# StressMonitor.net
KiCad netlist of a schematic drawn in Altium Designer
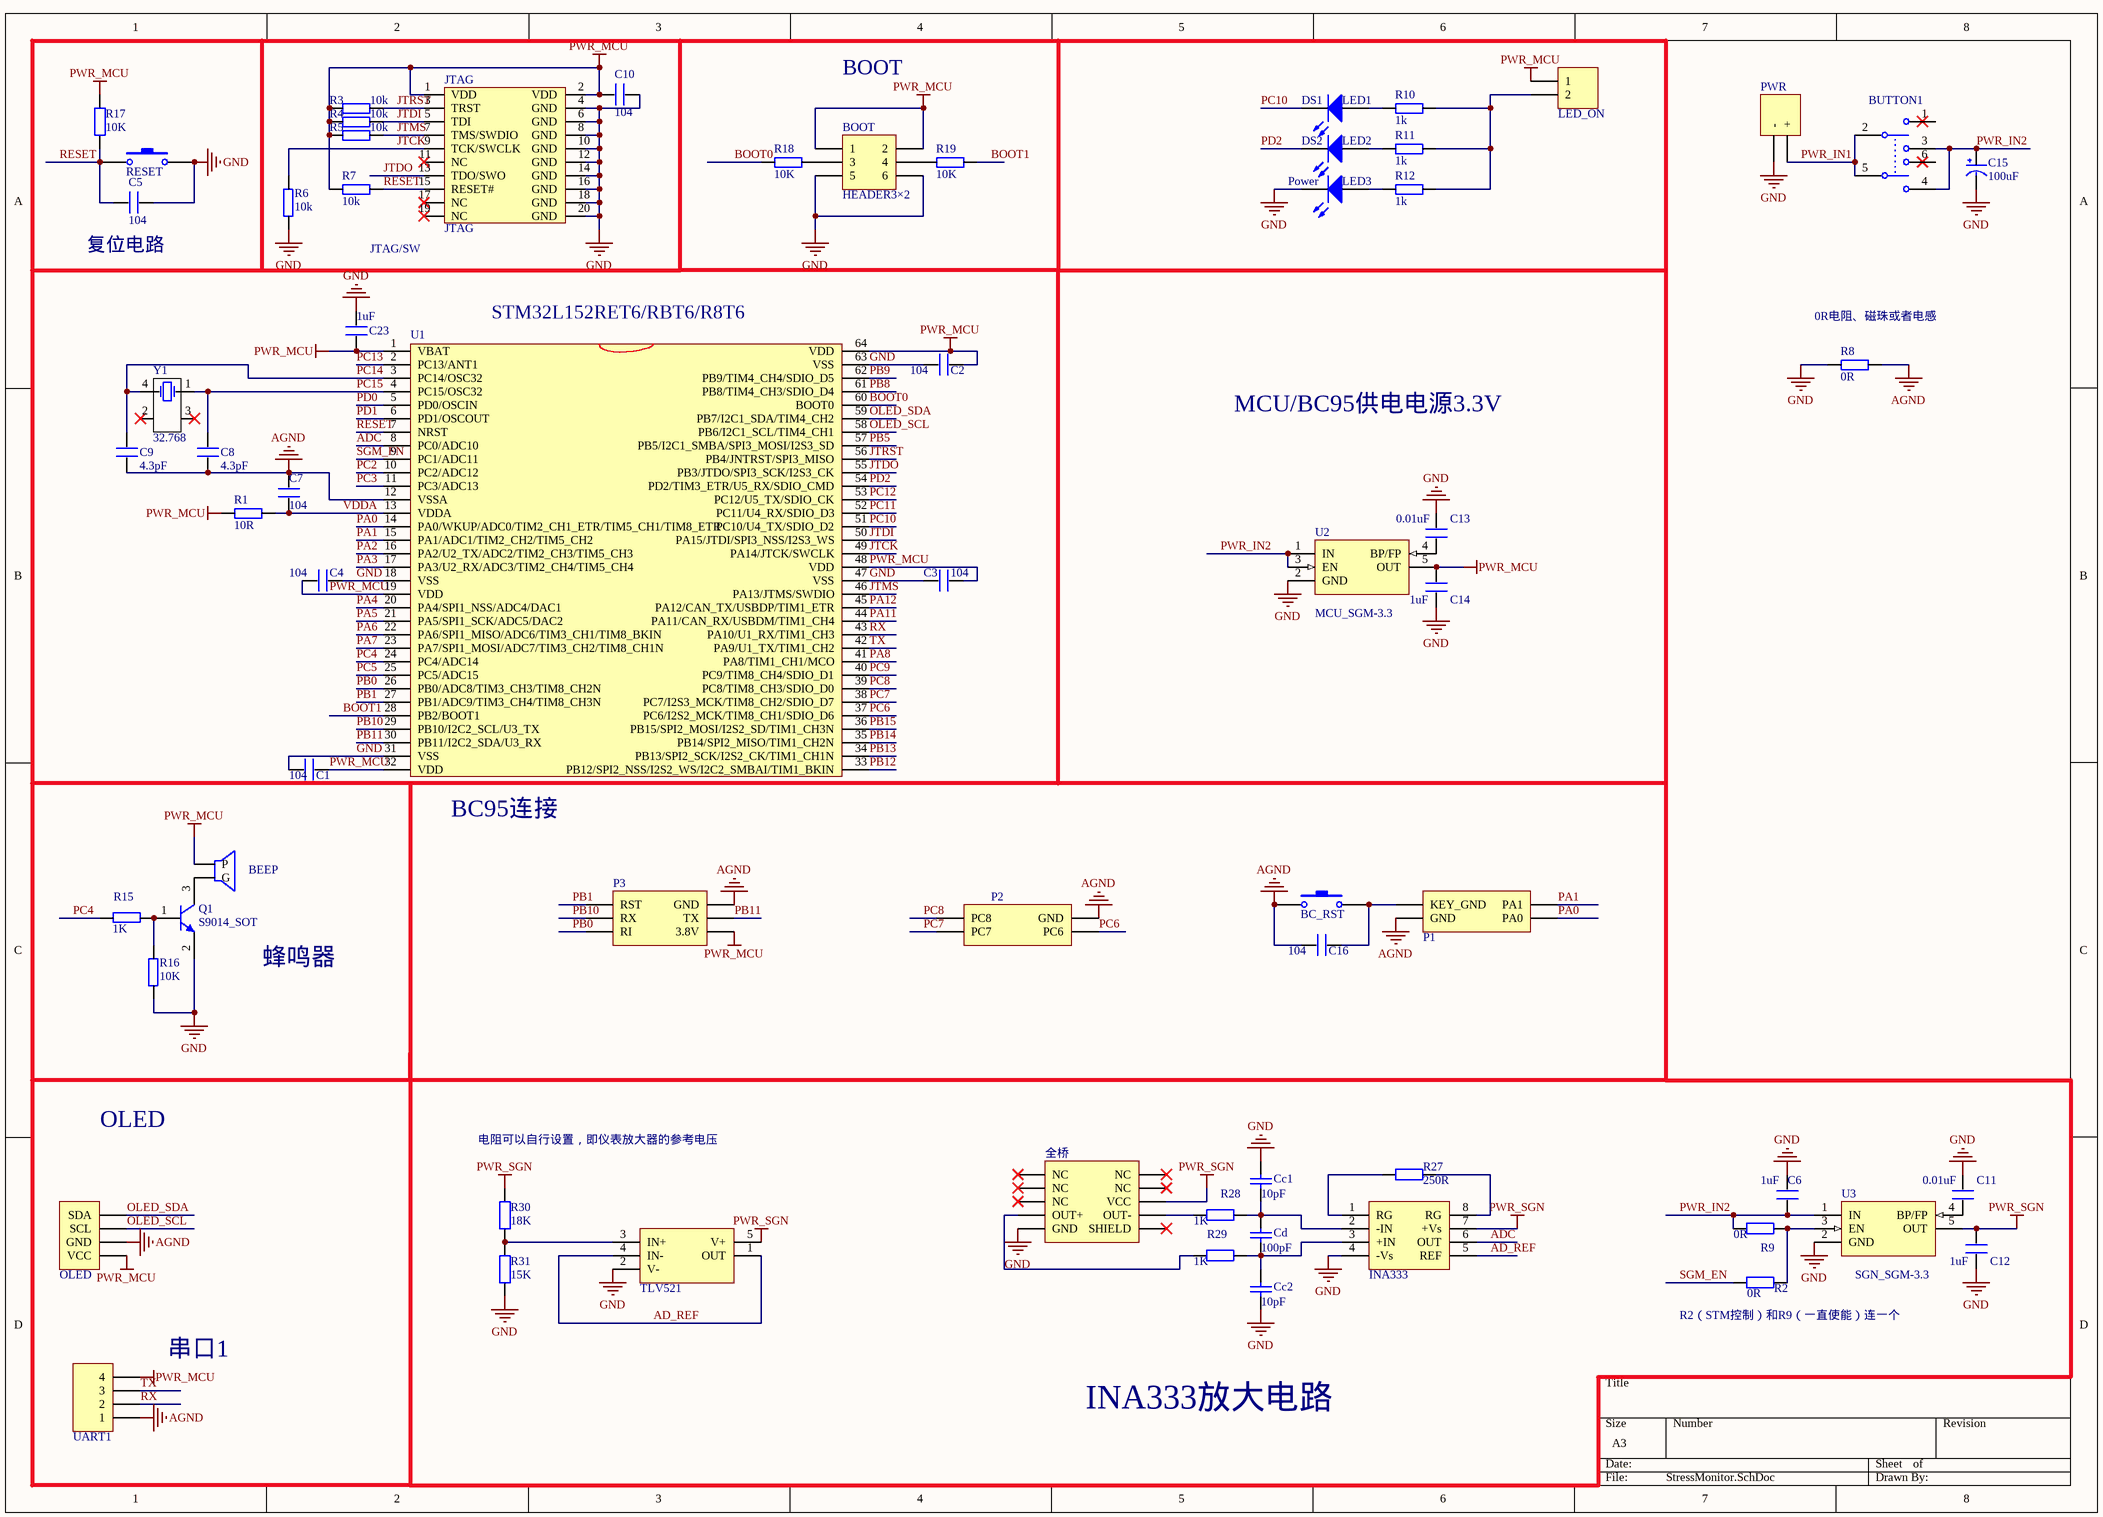
[diagram p0: StressMonitor.SchDoc]

(export (version "E")
  (design (tool "Eeschema 10.0.6"))
  (components
    (comp (ref "BC_RST")
      (value "SW-PB")
      (footprint "SW_PB2_A2")
      (description "微动开关")
      (fields (field (name "PUBLISHER") "Altium Limited"))
      (libsource (lib "Song") (part "SW-PB"))
    )
    (comp (ref "BEEP")
      (value "BEEP")
      (footprint "Beep")
      (libsource (lib "Explorer STM32F407封装库") (part "BEEP"))
    )
    (comp (ref "BOOT")
      (value "HEADER3×2")
      (footprint "HDR2X3")
      (description "Header, 3-Pin, Dual row")
      (fields (field (name "PUBLISHER") "Altium Limited"))
      (libsource (lib "MiniSTM32 V3.0封装库") (part "Header 3X2"))
    )
    (comp (ref "BUTTON1")
      (value "SW-DPDT1")
      (footprint "SWITCH_B2")
      (description "单刀双掷开关")
      (fields (field (name "PUBLISHER") "Altium Limited"))
      (libsource (lib "Song") (part "SW-DPDT"))
    )
    (comp (ref "C1") (value "104") (footprint "C-RAD-0603") (libsource (lib "MiniSTM32 V3.0封装库") (part "C")))
    (comp (ref "C2") (value "104") (footprint "C-RAD-0603") (libsource (lib "MiniSTM32 V3.0封装库") (part "C")))
    (comp (ref "C3") (value "104") (footprint "C-RAD-0603") (libsource (lib "MiniSTM32 V3.0封装库") (part "C")))
    (comp (ref "C4") (value "104") (footprint "C-RAD-0603") (libsource (lib "MiniSTM32 V3.0封装库") (part "C")))
    (comp (ref "C5") (value "104") (footprint "C-RAD-0603") (libsource (lib "MiniSTM32 V3.0封装库") (part "C")))
    (comp (ref "C6") (value "1uF") (footprint "C-RAD-0603") (libsource (lib "MiniSTM32 V3.0封装库") (part "C")))
    (comp (ref "C7") (value "104") (footprint "C-RAD-0603") (libsource (lib "MiniSTM32 V3.0封装库") (part "C")))
    (comp (ref "C8")
      (value "4.3pF")
      (footprint "C-RAD-0603")
      (libsource (lib "MiniSTM32 V3.0封装库") (part "C"))
    )
    (comp (ref "C9")
      (value "4.3pF")
      (footprint "C-RAD-0603")
      (libsource (lib "MiniSTM32 V3.0封装库") (part "C"))
    )
    (comp (ref "C10") (value "104") (footprint "C-RAD-0603") (libsource (lib "MiniSTM32 V3.0封装库") (part "C")))
    (comp (ref "C11")
      (value "0.01uF")
      (footprint "C-RAD-0603")
      (libsource (lib "MiniSTM32 V3.0封装库") (part "C"))
    )
    (comp (ref "C12") (value "1uF") (footprint "C-RAD-0603") (libsource (lib "MiniSTM32 V3.0封装库") (part "C")))
    (comp (ref "C13")
      (value "0.01uF")
      (footprint "C-RAD-0603")
      (libsource (lib "MiniSTM32 V3.0封装库") (part "C"))
    )
    (comp (ref "C14") (value "1uF") (footprint "C-RAD-0603") (libsource (lib "MiniSTM32 V3.0封装库") (part "C")))
    (comp (ref "C15")
      (value "100uF")
      (footprint "C-RB-S6")
      (libsource (lib "MiniSTM32 V3.0封装库") (part "CAP"))
    )
    (comp (ref "C16") (value "104") (footprint "C-RAD-0603") (libsource (lib "MiniSTM32 V3.0封装库") (part "C")))
    (comp (ref "C23") (value "1uF") (footprint "C-RAD-0603") (libsource (lib "MiniSTM32 V3.0封装库") (part "C")))
    (comp (ref "Cc1")
      (value "10pF")
      (footprint "C-RAD-0603")
      (description "无极性电容")
      (fields (field (name "Comment") "Cap") (field (name "PUBLISHER") "Altium Limited"))
      (libsource (lib "Song") (part "Cap"))
    )
    (comp (ref "Cc2")
      (value "10pF")
      (footprint "C-RAD-0603")
      (description "无极性电容")
      (fields (field (name "Comment") "Cap") (field (name "PUBLISHER") "Altium Limited"))
      (libsource (lib "Song") (part "Cap"))
    )
    (comp (ref "Cd")
      (value "100pF")
      (footprint "C-RAD-0603")
      (description "无极性电容")
      (fields (field (name "Comment") "Cap") (field (name "PUBLISHER") "Altium Limited"))
      (libsource (lib "Song") (part "Cap"))
    )
    (comp (ref "DS1")
      (value "LED1")
      (footprint "SMDLED")
      (description "Typical RED, GREEN, YELLOW, AMBER GaAs LED")
      (fields (field (name "PUBLISHER") "Altium Limited"))
      (libsource (lib "MiniSTM32 V3.0封装库") (part "LED2"))
    )
    (comp (ref "DS2")
      (value "LED2")
      (footprint "SMDLED")
      (description "Typical RED, GREEN, YELLOW, AMBER GaAs LED")
      (fields (field (name "PUBLISHER") "Altium Limited"))
      (libsource (lib "MiniSTM32 V3.0封装库") (part "LED2"))
    )
    (comp (ref "INA333")
      (value "AD620")
      (footprint "MSOP-MS8_M")
      (description "仪用放大器")
      (fields (field (name "PUBLISHER") "Altium Limited"))
      (libsource (lib "Song") (part "AD620"))
    )
    (comp (ref "JTAG")
      (value "JTAG")
      (footprint "JTAG_20")
      (libsource (lib "MiniSTM32 V3.0封装库") (part "JTAG"))
    )
    (comp (ref "LED_ON")
      (value "Header 2")
      (footprint "HDR2X1_A")
      (description "接插件")
      (fields (field (name "PUBLISHER") "Altium Limited"))
      (libsource (lib "") (part "Header 2_1"))
    )
    (comp (ref "OLED")
      (value "OLED")
      (footprint "HDR4X1_A")
      (fields (field (name "PUBLISHER") "Altium Limited"))
      (libsource (lib "Song") (part "OLED"))
    )
    (comp (ref "P1")
      (value "BC95_P1")
      (footprint "HDR2X2_A")
      (description "连接BC的GND等四个脚")
      (fields (field (name "PUBLISHER") "Altium Limited"))
      (libsource (lib "Song") (part "BC95_P1"))
    )
    (comp (ref "P2")
      (value "BC95_P2")
      (footprint "HDR2X2_A")
      (description "连接BC的GND等四个脚")
      (fields (field (name "PUBLISHER") "Altium Limited"))
      (libsource (lib "Song") (part "BC95_P2"))
    )
    (comp (ref "P3")
      (value "BC95_P3")
      (footprint "HDR3X2")
      (description "BC95的通信部分")
      (fields (field (name "PUBLISHER") "Altium Limited"))
      (libsource (lib "Song") (part "BC95_P3"))
    )
    (comp (ref "Power")
      (value "LED3")
      (footprint "SMDLED")
      (description "Typical RED, GREEN, YELLOW, AMBER GaAs LED")
      (fields (field (name "PUBLISHER") "Altium Limited"))
      (libsource (lib "MiniSTM32 V3.0封装库") (part "LED2"))
    )
    (comp (ref "PWR")
      (value "Header 2")
      (footprint "HDR2X1_A")
      (description "接插件")
      (fields (field (name "PUBLISHER") "Altium Limited"))
      (libsource (lib "Song") (part "Header 2"))
    )
    (comp (ref "Q1")
      (value "S9014_SOT")
      (footprint "SOT-23")
      (description "NPN三极管")
      (fields (field (name "PUBLISHER") "Altium Limited"))
      (libsource (lib "Song") (part "S9014_SOT"))
    )
    (comp (ref "R1") (value "10R") (footprint "0805-1") (libsource (lib "MiniSTM32 V3.0封装库") (part "R")))
    (comp (ref "R2")
      (value "Res1")
      (footprint "0805-1")
      (description "贴片电阻")
      (fields (field (name "NC") "0R") (field (name "PUBLISHER") "Altium Limited"))
      (libsource (lib "Song") (part "Res1"))
    )
    (comp (ref "R3") (value "10k") (footprint "0805-1") (libsource (lib "MiniSTM32 V3.0封装库") (part "R")))
    (comp (ref "R4") (value "10k") (footprint "0805-1") (libsource (lib "MiniSTM32 V3.0封装库") (part "R")))
    (comp (ref "R5") (value "10k") (footprint "0805-1") (libsource (lib "MiniSTM32 V3.0封装库") (part "R")))
    (comp (ref "R6") (value "10k") (footprint "0805-1") (libsource (lib "MiniSTM32 V3.0封装库") (part "R")))
    (comp (ref "R7") (value "10k") (footprint "0805-1") (libsource (lib "MiniSTM32 V3.0封装库") (part "R")))
    (comp (ref "R8") (value "0R") (footprint "0805-1") (libsource (lib "MiniSTM32 V3.0封装库") (part "R")))
    (comp (ref "R9")
      (value "Res1")
      (footprint "0805-1")
      (description "贴片电阻")
      (fields (field (name "NC") "0R") (field (name "PUBLISHER") "Altium Limited"))
      (libsource (lib "") (part "Res1_2"))
    )
    (comp (ref "R10") (value "1k") (footprint "0805-1") (libsource (lib "MiniSTM32 V3.0封装库") (part "R")))
    (comp (ref "R11") (value "1k") (footprint "0805-1") (libsource (lib "MiniSTM32 V3.0封装库") (part "R")))
    (comp (ref "R12") (value "1k") (footprint "0805-1") (libsource (lib "MiniSTM32 V3.0封装库") (part "R")))
    (comp (ref "R15") (value "1K") (footprint "0805-1") (libsource (lib "MiniSTM32 V3.0封装库") (part "R")))
    (comp (ref "R16") (value "10K") (footprint "0805-1") (libsource (lib "MiniSTM32 V3.0封装库") (part "R")))
    (comp (ref "R17")
      (value "10K")
      (footprint "0805-1")
      (description "贴片电阻")
      (fields (field (name "PUBLISHER") "Altium Limited"))
      (libsource (lib "") (part "Res1_1"))
    )
    (comp (ref "R18") (value "10K") (footprint "0805-1") (libsource (lib "MiniSTM32 V3.0封装库") (part "R")))
    (comp (ref "R19") (value "10K") (footprint "0805-1") (libsource (lib "MiniSTM32 V3.0封装库") (part "R")))
    (comp (ref "R27")
      (value "250R")
      (footprint "0805-1")
      (description "贴片电阻")
      (fields (field (name "Comment") "正式") (field (name "PUBLISHER") "Altium Limited"))
      (libsource (lib "Song") (part "Res1"))
    )
    (comp (ref "R28")
      (value "1K")
      (footprint "0805-1")
      (description "贴片电阻")
      (fields (field (name "Comment") "Res1") (field (name "PUBLISHER") "Altium Limited"))
      (libsource (lib "Song") (part "Res1"))
    )
    (comp (ref "R29")
      (value "1K")
      (footprint "0805-1")
      (description "贴片电阻")
      (fields (field (name "Comment") "Res1") (field (name "PUBLISHER") "Altium Limited"))
      (libsource (lib "Song") (part "Res1"))
    )
    (comp (ref "R30")
      (value "18K")
      (footprint "0805-1")
      (description "贴片电阻")
      (fields (field (name "PUBLISHER") "Altium Limited"))
      (libsource (lib "") (part "Res1_1"))
    )
    (comp (ref "R31")
      (value "15K")
      (footprint "0805-1")
      (description "贴片电阻")
      (fields (field (name "PUBLISHER") "Altium Limited"))
      (libsource (lib "") (part "Res1_1"))
    )
    (comp (ref "RESET")
      (value "SW-PB")
      (footprint "SW_PB2_A2")
      (description "微动开关")
      (fields (field (name "PUBLISHER") "Altium Limited"))
      (libsource (lib "Song") (part "SW-PB"))
    )
    (comp (ref "TLV521")
      (value "TLV521")
      (footprint "DCK-5")
      (description "低功耗稳压")
      (fields (field (name "PUBLISHER") "Altium Limited"))
      (libsource (lib "Song") (part "TLV521"))
    )
    (comp (ref "U1")
      (value "STM32L152RET6/RBT6/R8T6")
      (footprint "LQFP-64")
      (libsource (lib "MiniSTM32 V3.0封装库") (part "STM32F103RDT6"))
    )
    (comp (ref "U2")
      (value "SGM2036")
      (footprint "SOT23-5")
      (description "低功耗稳压")
      (fields (field (name "PUBLISHER") "Altium Limited"))
      (libsource (lib "Song") (part "SGM2036"))
    )
    (comp (ref "U3")
      (value "SGM2036")
      (footprint "SOT23-5")
      (description "低功耗稳压")
      (fields (field (name "PUBLISHER") "Altium Limited"))
      (libsource (lib "Song") (part "SGM2036"))
    )
    (comp (ref "UART1")
      (value "Header 4")
      (footprint "HDR4X1_A")
      (description "接插件")
      (fields (field (name "PUBLISHER") "Altium Limited"))
      (libsource (lib "Song") (part "Header 4"))
    )
    (comp (ref "Y1")
      (value "32.768")
      (footprint "XTAL_8x3.8")
      (description "贴片晶振")
      (fields (field (name "Comment") "XTAL_8x3.8"))
      (libsource (lib "Song") (part "XTAL_8x3.8"))
    )
    (comp (ref "全桥")
      (value "连接全桥")
      (footprint "HDR5*2_2mm")
      (description "全桥应变片插口;从TB购买")
      (fields (field (name "PUBLISHER") "Altium Limited"))
      (libsource (lib "Song") (part "StrainGage"))
    )
  )
  (nets
    (net (code "1") (name "/ADC") (class "Default")
      (node (ref "INA333") (pin "6") (pinfunction "OUT_6") (pintype "passive"))
      (node (ref "U1") (pin "8") (pinfunction "PC0/ADC10_8") (pintype "passive"))
    )
    (net (code "2") (name "/AD_REF") (class "Default")
      (node (ref "INA333") (pin "5") (pinfunction "REF_5") (pintype "passive"))
      (node (ref "TLV521") (pin "1") (pinfunction "OUT_1") (pintype "power_in"))
      (node (ref "TLV521") (pin "4") (pinfunction "IN-_4") (pintype "passive"))
    )
    (net (code "3") (name "/BOOT0") (class "Default")
      (node (ref "R18") (pin "1") (pintype "passive"))
      (node (ref "U1") (pin "60") (pinfunction "BOOT0_60") (pintype "passive"))
    )
    (net (code "4") (name "/BOOT1") (class "Default")
      (node (ref "R19") (pin "2") (pintype "passive"))
      (node (ref "U1") (pin "28") (pinfunction "PB2/BOOT1_28") (pintype "passive"))
    )
    (net (code "5") (name "/JTCK") (class "Default")
      (node (ref "JTAG") (pin "9") (pinfunction "TCK/SWCLK_9") (pintype "passive"))
      (node (ref "R6") (pin "1") (pintype "passive"))
      (node (ref "U1") (pin "49") (pinfunction "PA14/JTCK/SWCLK_49") (pintype "passive"))
    )
    (net (code "6") (name "/JTDI") (class "Default")
      (node (ref "JTAG") (pin "5") (pinfunction "TDI_5") (pintype "passive"))
      (node (ref "R4") (pin "2") (pintype "passive"))
      (node (ref "U1") (pin "50") (pinfunction "PA15/JTDI/SPI3_NSS/I2S3_WS_50") (pintype "passive"))
    )
    (net (code "7") (name "/JTDO") (class "Default")
      (node (ref "JTAG") (pin "13") (pinfunction "TDO/SWO_13") (pintype "passive"))
      (node (ref "U1") (pin "55") (pinfunction "PB3/JTDO/SPI3_SCK/I2S3_CK_55") (pintype "passive"))
    )
    (net (code "8") (name "/JTMS") (class "Default")
      (node (ref "JTAG") (pin "7") (pinfunction "TMS/SWDIO_7") (pintype "passive"))
      (node (ref "R5") (pin "2") (pintype "passive"))
      (node (ref "U1") (pin "46") (pinfunction "PA13/JTMS/SWDIO_46") (pintype "passive"))
    )
    (net (code "9") (name "/JTRST") (class "Default")
      (node (ref "JTAG") (pin "3") (pinfunction "TRST_3") (pintype "passive"))
      (node (ref "R3") (pin "2") (pintype "passive"))
      (node (ref "U1") (pin "56") (pinfunction "PB4/JNTRST/SPI3_MISO_56") (pintype "passive"))
    )
    (net (code "10") (name "/OLED_SCL") (class "Default")
      (node (ref "OLED") (pin "3") (pinfunction "SCL_3") (pintype "passive"))
      (node (ref "U1") (pin "58") (pinfunction "PB6/I2C1_SCL/TIM4_CH1_58") (pintype "passive"))
    )
    (net (code "11") (name "/OLED_SDA") (class "Default")
      (node (ref "OLED") (pin "4") (pinfunction "SDA_4") (pintype "passive"))
      (node (ref "U1") (pin "59") (pinfunction "PB7/I2C1_SDA/TIM4_CH2_59") (pintype "passive"))
    )
    (net (code "12") (name "/PA0") (class "Default")
      (node (ref "P1") (pin "3") (pinfunction "PA0_3") (pintype "passive"))
      (node (ref "U1") (pin "14") (pinfunction "PA0/WKUP/ADC0/TIM2_CH1_ETR/TIM5_CH1/TIM8_ETR_14") (pintype "passive"))
    )
    (net (code "13") (name "/PA1") (class "Default")
      (node (ref "P1") (pin "4") (pinfunction "PA1_4") (pintype "passive"))
      (node (ref "U1") (pin "15") (pinfunction "PA1/ADC1/TIM2_CH2/TIM5_CH2_15") (pintype "passive"))
    )
    (net (code "14") (name "/PA2") (class "Default")
      (node (ref "U1") (pin "16") (pinfunction "PA2/U2_TX/ADC2/TIM2_CH3/TIM5_CH3_16") (pintype "passive"))
    )
    (net (code "15") (name "/PA3") (class "Default")
      (node (ref "U1") (pin "17") (pinfunction "PA3/U2_RX/ADC3/TIM2_CH4/TIM5_CH4_17") (pintype "passive"))
    )
    (net (code "16") (name "/PA4") (class "Default")
      (node (ref "U1") (pin "20") (pinfunction "PA4/SPI1_NSS/ADC4/DAC1_20") (pintype "passive"))
    )
    (net (code "17") (name "/PA5") (class "Default")
      (node (ref "U1") (pin "21") (pinfunction "PA5/SPI1_SCK/ADC5/DAC2_21") (pintype "passive"))
    )
    (net (code "18") (name "/PA6") (class "Default")
      (node (ref "U1") (pin "22") (pinfunction "PA6/SPI1_MISO/ADC6/TIM3_CH1/TIM8_BKIN_22") (pintype "passive"))
    )
    (net (code "19") (name "/PA7") (class "Default")
      (node (ref "U1") (pin "23") (pinfunction "PA7/SPI1_MOSI/ADC7/TIM3_CH2/TIM8_CH1N_23") (pintype "passive"))
    )
    (net (code "20") (name "/PA8") (class "Default")
      (node (ref "U1") (pin "41") (pinfunction "PA8/TIM1_CH1/MCO_41") (pintype "passive"))
    )
    (net (code "21") (name "/PA11") (class "Default")
      (node (ref "U1") (pin "44") (pinfunction "PA11/CAN_RX/USBDM/TIM1_CH4_44") (pintype "passive"))
    )
    (net (code "22") (name "/PA12") (class "Default")
      (node (ref "U1") (pin "45") (pinfunction "PA12/CAN_TX/USBDP/TIM1_ETR_45") (pintype "passive"))
    )
    (net (code "23") (name "/PB0") (class "Default")
      (node (ref "P3") (pin "3") (pinfunction "RI_3") (pintype "passive"))
      (node (ref "U1") (pin "26") (pinfunction "PB0/ADC8/TIM3_CH3/TIM8_CH2N_26") (pintype "passive"))
    )
    (net (code "24") (name "/PB1") (class "Default")
      (node (ref "P3") (pin "1") (pinfunction "RST_1") (pintype "passive"))
      (node (ref "U1") (pin "27") (pinfunction "PB1/ADC9/TIM3_CH4/TIM8_CH3N_27") (pintype "passive"))
    )
    (net (code "25") (name "/PB5") (class "Default")
      (node (ref "U1") (pin "57") (pinfunction "PB5/I2C1_SMBA/SPI3_MOSI/I2S3_SD_57") (pintype "passive"))
    )
    (net (code "26") (name "/PB8") (class "Default")
      (node (ref "U1") (pin "61") (pinfunction "PB8/TIM4_CH3/SDIO_D4_61") (pintype "passive"))
    )
    (net (code "27") (name "/PB9") (class "Default")
      (node (ref "U1") (pin "62") (pinfunction "PB9/TIM4_CH4/SDIO_D5_62") (pintype "passive"))
    )
    (net (code "28") (name "/PB10") (class "Default")
      (node (ref "P3") (pin "2") (pinfunction "RX_2") (pintype "passive"))
      (node (ref "U1") (pin "29") (pinfunction "PB10/I2C2_SCL/U3_TX_29") (pintype "passive"))
    )
    (net (code "29") (name "/PB11") (class "Default")
      (node (ref "P3") (pin "5") (pinfunction "TX_5") (pintype "passive"))
      (node (ref "U1") (pin "30") (pinfunction "PB11/I2C2_SDA/U3_RX_30") (pintype "passive"))
    )
    (net (code "30") (name "/PB12") (class "Default")
      (node (ref "U1") (pin "33") (pinfunction "PB12/SPI2_NSS/I2S2_WS/I2C2_SMBAI/TIM1_BKIN_33") (pintype "passive"))
    )
    (net (code "31") (name "/PB13") (class "Default")
      (node (ref "U1") (pin "34") (pinfunction "PB13/SPI2_SCK/I2S2_CK/TIM1_CH1N_34") (pintype "passive"))
    )
    (net (code "32") (name "/PB14") (class "Default")
      (node (ref "U1") (pin "35") (pinfunction "PB14/SPI2_MISO/TIM1_CH2N_35") (pintype "passive"))
    )
    (net (code "33") (name "/PB15") (class "Default")
      (node (ref "U1") (pin "36") (pinfunction "PB15/SPI2_MOSI/I2S2_SD/TIM1_CH3N_36") (pintype "passive"))
    )
    (net (code "34") (name "/PC2") (class "Default")
      (node (ref "U1") (pin "10") (pinfunction "PC2/ADC12_10") (pintype "passive"))
    )
    (net (code "35") (name "/PC3") (class "Default")
      (node (ref "U1") (pin "11") (pinfunction "PC3/ADC13_11") (pintype "passive"))
    )
    (net (code "36") (name "/PC4") (class "Default")
      (node (ref "R15") (pin "2") (pintype "passive"))
      (node (ref "U1") (pin "24") (pinfunction "PC4/ADC14_24") (pintype "passive"))
    )
    (net (code "37") (name "/PC5") (class "Default")
      (node (ref "U1") (pin "25") (pinfunction "PC5/ADC15_25") (pintype "passive"))
    )
    (net (code "38") (name "/PC6") (class "Default")
      (node (ref "P2") (pin "3") (pinfunction "PC6_3") (pintype "passive"))
      (node (ref "U1") (pin "37") (pinfunction "PC6/I2S2_MCK/TIM8_CH1/SDIO_D6_37") (pintype "passive"))
    )
    (net (code "39") (name "/PC7") (class "Default")
      (node (ref "P2") (pin "2") (pinfunction "PC7_2") (pintype "passive"))
      (node (ref "U1") (pin "38") (pinfunction "PC7/I2S3_MCK/TIM8_CH2/SDIO_D7_38") (pintype "passive"))
    )
    (net (code "40") (name "/PC8") (class "Default")
      (node (ref "P2") (pin "1") (pinfunction "PC8_1") (pintype "passive"))
      (node (ref "U1") (pin "39") (pinfunction "PC8/TIM8_CH3/SDIO_D0_39") (pintype "passive"))
    )
    (net (code "41") (name "/PC9") (class "Default")
      (node (ref "U1") (pin "40") (pinfunction "PC9/TIM8_CH4/SDIO_D1_40") (pintype "passive"))
    )
    (net (code "42") (name "/PC10") (class "Default")
      (node (ref "DS1") (pin "2") (pinfunction "K_2") (pintype "passive"))
      (node (ref "U1") (pin "51") (pinfunction "PC10/U4_TX/SDIO_D2_51") (pintype "passive"))
    )
    (net (code "43") (name "/PC11") (class "Default")
      (node (ref "U1") (pin "52") (pinfunction "PC11/U4_RX/SDIO_D3_52") (pintype "passive"))
    )
    (net (code "44") (name "/PC12") (class "Default")
      (node (ref "U1") (pin "53") (pinfunction "PC12/U5_TX/SDIO_CK_53") (pintype "passive"))
    )
    (net (code "45") (name "/PC13") (class "Default")
      (node (ref "U1") (pin "2") (pinfunction "PC13/ANT1_2") (pintype "passive"))
    )
    (net (code "46") (name "/PC14") (class "Default")
      (node (ref "C9") (pin "2") (pintype "passive"))
      (node (ref "U1") (pin "3") (pinfunction "PC14/OSC32_3") (pintype "passive"))
      (node (ref "Y1") (pin "4") (pinfunction "OSC1_4") (pintype "passive"))
    )
    (net (code "47") (name "/PC15") (class "Default")
      (node (ref "C8") (pin "2") (pintype "passive"))
      (node (ref "U1") (pin "4") (pinfunction "PC15/OSC32_4") (pintype "passive"))
      (node (ref "Y1") (pin "1") (pinfunction "OSC2_1") (pintype "passive"))
    )
    (net (code "48") (name "/PD0") (class "Default")
      (node (ref "U1") (pin "5") (pinfunction "PD0/OSCIN_5") (pintype "passive"))
    )
    (net (code "49") (name "/PD1") (class "Default")
      (node (ref "U1") (pin "6") (pinfunction "PD1/OSCOUT_6") (pintype "passive"))
    )
    (net (code "50") (name "/PD2") (class "Default")
      (node (ref "DS2") (pin "2") (pinfunction "K_2") (pintype "passive"))
      (node (ref "U1") (pin "54") (pinfunction "PD2/TIM3_ETR/U5_RX/SDIO_CMD_54") (pintype "passive"))
    )
    (net (code "51") (name "/PWR_IN1") (class "Default")
      (node (ref "BUTTON1") (pin "2") (pinfunction "2_2") (pintype "passive"))
      (node (ref "BUTTON1") (pin "5") (pinfunction "5_5") (pintype "passive"))
      (node (ref "PWR") (pin "2") (pinfunction "+_2") (pintype "passive"))
    )
    (net (code "52") (name "/PWR_IN2") (class "Default")
      (node (ref "BUTTON1") (pin "3") (pinfunction "3_3") (pintype "passive"))
      (node (ref "BUTTON1") (pin "4") (pinfunction "4_4") (pintype "passive"))
      (node (ref "C15") (pin "1") (pinfunction "VCC_1") (pintype "passive"))
      (node (ref "C6") (pin "1") (pintype "passive"))
      (node (ref "R9") (pin "2") (pinfunction "2_2") (pintype "passive"))
      (node (ref "U2") (pin "1") (pinfunction "IN_1") (pintype "power_in"))
      (node (ref "U2") (pin "3") (pinfunction "EN_3") (pintype "input"))
      (node (ref "U3") (pin "1") (pinfunction "IN_1") (pintype "power_in"))
    )
    (net (code "53") (name "/RESET") (class "Default")
      (node (ref "C5") (pin "1") (pintype "passive"))
      (node (ref "JTAG") (pin "15") (pinfunction "RESET#_15") (pintype "passive"))
      (node (ref "R17") (pin "1") (pinfunction "1_1") (pintype "passive"))
      (node (ref "R7") (pin "2") (pintype "passive"))
      (node (ref "RESET") (pin "1") (pinfunction "1_1") (pintype "passive"))
      (node (ref "U1") (pin "7") (pinfunction "NRST_7") (pintype "passive"))
    )
    (net (code "54") (name "/RX") (class "Default")
      (node (ref "U1") (pin "43") (pinfunction "PA10/U1_RX/TIM1_CH3_43") (pintype "passive"))
      (node (ref "UART1") (pin "2") (pinfunction "2_2") (pintype "passive"))
    )
    (net (code "55") (name "/SGM_EN") (class "Default")
      (node (ref "R2") (pin "1") (pinfunction "1_1") (pintype "passive"))
      (node (ref "U1") (pin "9") (pinfunction "PC1/ADC11_9") (pintype "passive"))
    )
    (net (code "56") (name "/TX") (class "Default")
      (node (ref "U1") (pin "42") (pinfunction "PA9/U1_TX/TIM1_CH2_42") (pintype "passive"))
      (node (ref "UART1") (pin "3") (pinfunction "3_3") (pintype "passive"))
    )
    (net (code "57") (name "/VDDA") (class "Default")
      (node (ref "C7") (pin "1") (pintype "passive"))
      (node (ref "R1") (pin "2") (pintype "passive"))
      (node (ref "U1") (pin "13") (pinfunction "VDDA_13") (pintype "passive"))
    )
    (net (code "58") (name "AGND") (class "Default")
      (node (ref "BC_RST") (pin "1") (pinfunction "1_1") (pintype "passive"))
      (node (ref "C16") (pin "1") (pintype "passive"))
      (node (ref "C7") (pin "2") (pintype "passive"))
      (node (ref "C8") (pin "1") (pintype "passive"))
      (node (ref "C9") (pin "1") (pintype "passive"))
      (node (ref "OLED") (pin "2") (pinfunction "GND_2") (pintype "passive"))
      (node (ref "P1") (pin "2") (pinfunction "GND_2") (pintype "passive"))
      (node (ref "P2") (pin "4") (pinfunction "GND_4") (pintype "passive"))
      (node (ref "P3") (pin "6") (pinfunction "GND_6") (pintype "passive"))
      (node (ref "R8") (pin "2") (pintype "passive"))
      (node (ref "U1") (pin "12") (pinfunction "VSSA_12") (pintype "passive"))
      (node (ref "UART1") (pin "1") (pinfunction "1_1") (pintype "passive"))
    )
    (net (code "59") (name "GND") (class "Default")
      (node (ref "BOOT") (pin "5") (pinfunction "5_5") (pintype "passive"))
      (node (ref "BOOT") (pin "6") (pinfunction "6_6") (pintype "passive"))
      (node (ref "C1") (pin "1") (pintype "passive"))
      (node (ref "C10") (pin "2") (pintype "passive"))
      (node (ref "C11") (pin "2") (pintype "passive"))
      (node (ref "C12") (pin "1") (pintype "passive"))
      (node (ref "C13") (pin "2") (pintype "passive"))
      (node (ref "C14") (pin "1") (pintype "passive"))
      (node (ref "C15") (pin "2") (pinfunction "GND_2") (pintype "passive"))
      (node (ref "C2") (pin "1") (pintype "passive"))
      (node (ref "C23") (pin "1") (pintype "passive"))
      (node (ref "C3") (pin "1") (pintype "passive"))
      (node (ref "C4") (pin "2") (pintype "passive"))
      (node (ref "C5") (pin "2") (pintype "passive"))
      (node (ref "C6") (pin "2") (pintype "passive"))
      (node (ref "Cc1") (pin "2") (pinfunction "2_2") (pintype "passive"))
      (node (ref "Cc2") (pin "1") (pinfunction "1_1") (pintype "passive"))
      (node (ref "INA333") (pin "4") (pinfunction "-Vs_4") (pintype "passive"))
      (node (ref "JTAG") (pin "10") (pinfunction "GND_10") (pintype "passive"))
      (node (ref "JTAG") (pin "12") (pinfunction "GND_12") (pintype "passive"))
      (node (ref "JTAG") (pin "14") (pinfunction "GND_14") (pintype "passive"))
      (node (ref "JTAG") (pin "16") (pinfunction "GND_16") (pintype "passive"))
      (node (ref "JTAG") (pin "18") (pinfunction "GND_18") (pintype "passive"))
      (node (ref "JTAG") (pin "20") (pinfunction "GND_20") (pintype "passive"))
      (node (ref "JTAG") (pin "4") (pinfunction "GND_4") (pintype "passive"))
      (node (ref "JTAG") (pin "6") (pinfunction "GND_6") (pintype "passive"))
      (node (ref "JTAG") (pin "8") (pinfunction "GND_8") (pintype "passive"))
      (node (ref "PWR") (pin "1") (pinfunction "-_1") (pintype "passive"))
      (node (ref "Power") (pin "2") (pinfunction "K_2") (pintype "passive"))
      (node (ref "Q1") (pin "2") (pinfunction "E_2") (pintype "passive"))
      (node (ref "R16") (pin "2") (pintype "passive"))
      (node (ref "R31") (pin "1") (pinfunction "1_1") (pintype "passive"))
      (node (ref "R6") (pin "2") (pintype "passive"))
      (node (ref "R8") (pin "1") (pintype "passive"))
      (node (ref "RESET") (pin "2") (pinfunction "2_2") (pintype "passive"))
      (node (ref "TLV521") (pin "2") (pinfunction "V-_2") (pintype "power_in"))
      (node (ref "U1") (pin "18") (pinfunction "VSS_18") (pintype "passive"))
      (node (ref "U1") (pin "31") (pinfunction "VSS_31") (pintype "passive"))
      (node (ref "U1") (pin "47") (pinfunction "VSS_47") (pintype "passive"))
      (node (ref "U1") (pin "63") (pinfunction "VSS_63") (pintype "passive"))
      (node (ref "U2") (pin "2") (pinfunction "GND_2") (pintype "power_in"))
      (node (ref "U3") (pin "2") (pinfunction "GND_2") (pintype "power_in"))
      (node (ref "全桥") (pin "9") (pinfunction "GND_9") (pintype "passive"))
    )
    (net (code "60") (name "Net-(BEEP-G)") (class "Default")
      (node (ref "BEEP") (pin "2") (pinfunction "G_2") (pintype "passive"))
      (node (ref "Q1") (pin "3") (pinfunction "C_3") (pintype "passive"))
    )
    (net (code "61") (name "Net-(BOOT-Pad3)") (class "Default")
      (node (ref "BOOT") (pin "3") (pinfunction "3_3") (pintype "passive"))
      (node (ref "R18") (pin "2") (pintype "passive"))
    )
    (net (code "62") (name "Net-(BOOT-Pad4)") (class "Default")
      (node (ref "BOOT") (pin "4") (pinfunction "4_4") (pintype "passive"))
      (node (ref "R19") (pin "1") (pintype "passive"))
    )
    (net (code "63") (name "Net-(DS1-A)") (class "Default")
      (node (ref "DS1") (pin "1") (pinfunction "A_1") (pintype "passive"))
      (node (ref "R10") (pin "1") (pintype "passive"))
    )
    (net (code "64") (name "Net-(DS2-A)") (class "Default")
      (node (ref "DS2") (pin "1") (pinfunction "A_1") (pintype "passive"))
      (node (ref "R11") (pin "1") (pintype "passive"))
    )
    (net (code "65") (name "Net-(INA333-+IN)") (class "Default")
      (node (ref "Cc2") (pin "2") (pinfunction "2_2") (pintype "passive"))
      (node (ref "Cd") (pin "1") (pinfunction "1_1") (pintype "passive"))
      (node (ref "INA333") (pin "3") (pinfunction "+IN_3") (pintype "passive"))
      (node (ref "R29") (pin "2") (pinfunction "2_2") (pintype "passive"))
    )
    (net (code "66") (name "Net-(INA333--IN)") (class "Default")
      (node (ref "Cc1") (pin "1") (pinfunction "1_1") (pintype "passive"))
      (node (ref "Cd") (pin "2") (pinfunction "2_2") (pintype "passive"))
      (node (ref "INA333") (pin "2") (pinfunction "-IN_2") (pintype "passive"))
      (node (ref "R28") (pin "2") (pinfunction "2_2") (pintype "passive"))
    )
    (net (code "67") (name "Net-(INA333-RG-Pad1)") (class "Default")
      (node (ref "INA333") (pin "1") (pinfunction "RG_1") (pintype "passive"))
      (node (ref "R27") (pin "1") (pinfunction "1_1") (pintype "passive"))
    )
    (net (code "68") (name "Net-(INA333-RG-Pad8)") (class "Default")
      (node (ref "INA333") (pin "8") (pinfunction "RG_8") (pintype "passive"))
      (node (ref "R27") (pin "2") (pinfunction "2_2") (pintype "passive"))
    )
    (net (code "69") (name "Net-(LED_ON-Pad2)") (class "Default")
      (node (ref "LED_ON") (pin "2") (pinfunction "2_2") (pintype "passive"))
      (node (ref "R10") (pin "2") (pintype "passive"))
      (node (ref "R11") (pin "2") (pintype "passive"))
      (node (ref "R12") (pin "2") (pintype "passive"))
    )
    (net (code "70") (name "Net-(P1-KEY_GND)") (class "Default")
      (node (ref "BC_RST") (pin "2") (pinfunction "2_2") (pintype "passive"))
      (node (ref "C16") (pin "2") (pintype "passive"))
      (node (ref "P1") (pin "1") (pinfunction "KEY_GND_1") (pintype "passive"))
    )
    (net (code "71") (name "Net-(Power-A)") (class "Default")
      (node (ref "Power") (pin "1") (pinfunction "A_1") (pintype "passive"))
      (node (ref "R12") (pin "1") (pintype "passive"))
    )
    (net (code "72") (name "Net-(Q1-B)") (class "Default")
      (node (ref "Q1") (pin "1") (pinfunction "B_1") (pintype "passive"))
      (node (ref "R15") (pin "1") (pintype "passive"))
      (node (ref "R16") (pin "1") (pintype "passive"))
    )
    (net (code "73") (name "Net-(TLV521-IN+)") (class "Default")
      (node (ref "R30") (pin "1") (pinfunction "1_1") (pintype "passive"))
      (node (ref "R31") (pin "2") (pinfunction "2_2") (pintype "passive"))
      (node (ref "TLV521") (pin "3") (pinfunction "IN+_3") (pintype "passive"))
    )
    (net (code "74") (name "Net-(U2-BP{slash}FP)") (class "Default")
      (node (ref "C13") (pin "1") (pintype "passive"))
      (node (ref "U2") (pin "4") (pinfunction "BP/FP_4") (pintype "input"))
    )
    (net (code "75") (name "Net-(U3-BP{slash}FP)") (class "Default")
      (node (ref "C11") (pin "1") (pintype "passive"))
      (node (ref "U3") (pin "4") (pinfunction "BP/FP_4") (pintype "input"))
    )
    (net (code "76") (name "Net-(U3-EN)") (class "Default")
      (node (ref "R2") (pin "2") (pinfunction "2_2") (pintype "passive"))
      (node (ref "R9") (pin "1") (pinfunction "1_1") (pintype "passive"))
      (node (ref "U3") (pin "3") (pinfunction "EN_3") (pintype "input"))
    )
    (net (code "77") (name "Net-(全桥-OUT+)") (class "Default")
      (node (ref "R29") (pin "1") (pinfunction "1_1") (pintype "passive"))
      (node (ref "全桥") (pin "7") (pinfunction "OUT+_7") (pintype "passive"))
    )
    (net (code "78") (name "Net-(全桥-OUT-)") (class "Default")
      (node (ref "R28") (pin "1") (pinfunction "1_1") (pintype "passive"))
      (node (ref "全桥") (pin "8") (pinfunction "OUT-_8") (pintype "passive"))
    )
    (net (code "79") (name "PWR_MCU") (class "Default")
      (node (ref "BEEP") (pin "1") (pinfunction "P_1") (pintype "passive"))
      (node (ref "BOOT") (pin "1") (pinfunction "1_1") (pintype "passive"))
      (node (ref "BOOT") (pin "2") (pinfunction "2_2") (pintype "passive"))
      (node (ref "C1") (pin "2") (pintype "passive"))
      (node (ref "C10") (pin "1") (pintype "passive"))
      (node (ref "C14") (pin "2") (pintype "passive"))
      (node (ref "C2") (pin "2") (pintype "passive"))
      (node (ref "C23") (pin "2") (pintype "passive"))
      (node (ref "C3") (pin "2") (pintype "passive"))
      (node (ref "C4") (pin "1") (pintype "passive"))
      (node (ref "JTAG") (pin "1") (pinfunction "VDD_1") (pintype "passive"))
      (node (ref "JTAG") (pin "2") (pinfunction "VDD_2") (pintype "passive"))
      (node (ref "LED_ON") (pin "1") (pinfunction "1_1") (pintype "passive"))
      (node (ref "OLED") (pin "1") (pinfunction "VCC_1") (pintype "passive"))
      (node (ref "P3") (pin "4") (pinfunction "3.8V_4") (pintype "passive"))
      (node (ref "R1") (pin "1") (pintype "passive"))
      (node (ref "R17") (pin "2") (pinfunction "2_2") (pintype "passive"))
      (node (ref "R3") (pin "1") (pintype "passive"))
      (node (ref "R4") (pin "1") (pintype "passive"))
      (node (ref "R5") (pin "1") (pintype "passive"))
      (node (ref "R7") (pin "1") (pintype "passive"))
      (node (ref "U1") (pin "1") (pinfunction "VBAT_1") (pintype "passive"))
      (node (ref "U1") (pin "19") (pinfunction "VDD_19") (pintype "passive"))
      (node (ref "U1") (pin "32") (pinfunction "VDD_32") (pintype "passive"))
      (node (ref "U1") (pin "48") (pinfunction "VDD_48") (pintype "passive"))
      (node (ref "U1") (pin "64") (pinfunction "VDD_64") (pintype "passive"))
      (node (ref "U2") (pin "5") (pinfunction "OUT_5") (pintype "power_in"))
      (node (ref "UART1") (pin "4") (pinfunction "4_4") (pintype "passive"))
    )
    (net (code "80") (name "PWR_SGN") (class "Default")
      (node (ref "C12") (pin "2") (pintype "passive"))
      (node (ref "INA333") (pin "7") (pinfunction "+Vs_7") (pintype "passive"))
      (node (ref "R30") (pin "2") (pinfunction "2_2") (pintype "passive"))
      (node (ref "TLV521") (pin "5") (pinfunction "V+_5") (pintype "power_in"))
      (node (ref "U3") (pin "5") (pinfunction "OUT_5") (pintype "power_in"))
      (node (ref "全桥") (pin "6") (pinfunction "VCC_6") (pintype "passive"))
    )
    (net (code "81") (name "unconnected-(BUTTON1-Pad1)") (class "Default")
      (node (ref "BUTTON1") (pin "1") (pinfunction "1_1") (pintype "passive"))
    )
    (net (code "82") (name "unconnected-(BUTTON1-Pad6)") (class "Default")
      (node (ref "BUTTON1") (pin "6") (pinfunction "6_6") (pintype "passive"))
    )
    (net (code "83") (name "unconnected-(JTAG-NC-Pad11)") (class "Default")
      (node (ref "JTAG") (pin "11") (pinfunction "NC_11") (pintype "passive+no_connect"))
    )
    (net (code "84") (name "unconnected-(JTAG-NC-Pad17)") (class "Default")
      (node (ref "JTAG") (pin "17") (pinfunction "NC_17") (pintype "passive+no_connect"))
    )
    (net (code "85") (name "unconnected-(JTAG-NC-Pad19)") (class "Default")
      (node (ref "JTAG") (pin "19") (pinfunction "NC_19") (pintype "passive+no_connect"))
    )
    (net (code "86") (name "unconnected-(Y1-NC-Pad2)") (class "Default")
      (node (ref "Y1") (pin "2") (pinfunction "NC_2") (pintype "passive+no_connect"))
    )
    (net (code "87") (name "unconnected-(Y1-NC-Pad3)") (class "Default")
      (node (ref "Y1") (pin "3") (pinfunction "NC_3") (pintype "passive+no_connect"))
    )
    (net (code "88") (name "unconnected-(全桥-NC-Pad1)") (class "Default")
      (node (ref "全桥") (pin "1") (pinfunction "NC_1") (pintype "passive+no_connect"))
    )
    (net (code "89") (name "unconnected-(全桥-NC-Pad2)") (class "Default")
      (node (ref "全桥") (pin "2") (pinfunction "NC_2") (pintype "passive+no_connect"))
    )
    (net (code "90") (name "unconnected-(全桥-NC-Pad3)") (class "Default")
      (node (ref "全桥") (pin "3") (pinfunction "NC_3") (pintype "passive+no_connect"))
    )
    (net (code "91") (name "unconnected-(全桥-NC-Pad4)") (class "Default")
      (node (ref "全桥") (pin "4") (pinfunction "NC_4") (pintype "passive+no_connect"))
    )
    (net (code "92") (name "unconnected-(全桥-NC-Pad5)") (class "Default")
      (node (ref "全桥") (pin "5") (pinfunction "NC_5") (pintype "passive+no_connect"))
    )
    (net (code "93") (name "unconnected-(全桥-SHIELD-Pad10)") (class "Default")
      (node (ref "全桥") (pin "10") (pinfunction "SHIELD_10") (pintype "passive+no_connect"))
    )
  )
)
